# 04_Motor.net
KiCad netlist of a schematic drawn in Altium Designer
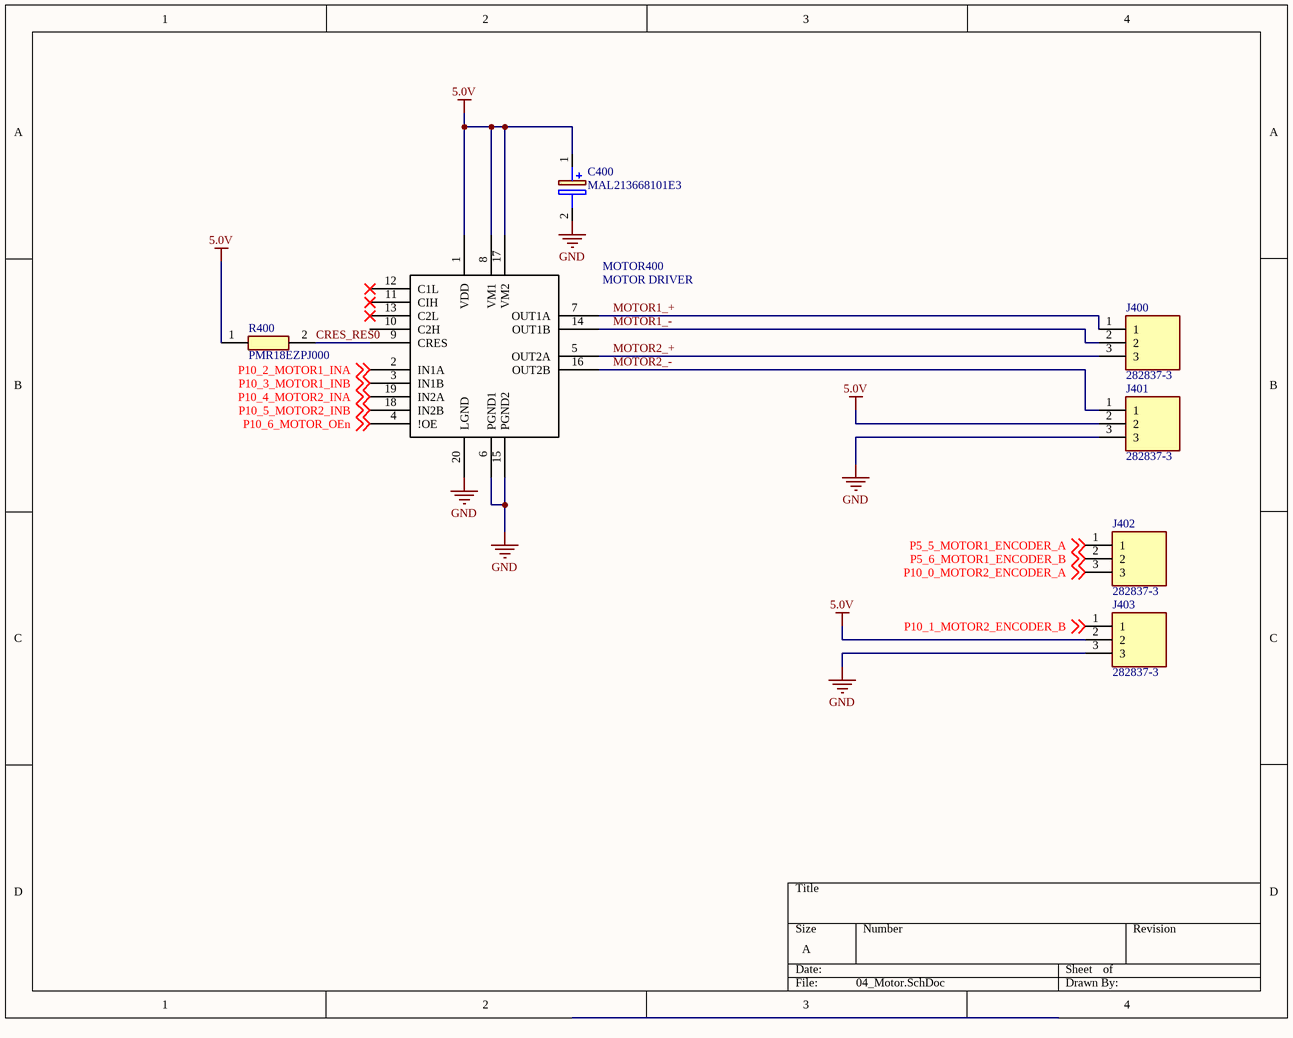
[diagram p0: 04_Motor.SchDoc]

(export (version "E")
  (design (tool "Eeschema 10.0.6"))
  (components
    (comp (ref "C400")
      (value "MAL213668101E3")
      (footprint "SamacSys:CAPPRD500W60D1050H1750")
      (description "Capacitor Polarised")
      (libsource (lib "100ufElectrolyticCap") (part "MAL213668101E3"))
    )
    (comp (ref "J400")
      (value "282837-3")
      (footprint "SamacSys:2828373")
      (description "Connector")
      (libsource (lib "3PinConnector") (part "282837-3"))
    )
    (comp (ref "J401")
      (value "282837-3")
      (footprint "SamacSys:2828373")
      (description "Connector")
      (libsource (lib "3PinConnector") (part "282837-3"))
    )
    (comp (ref "J402")
      (value "282837-3")
      (footprint "SamacSys:2828373")
      (description "Connector")
      (libsource (lib "3PinConnector") (part "282837-3"))
    )
    (comp (ref "J403")
      (value "282837-3")
      (footprint "SamacSys:2828373")
      (description "Connector")
      (libsource (lib "3PinConnector") (part "282837-3"))
    )
    (comp (ref "MOTOR400")
      (value "MOTOR DRIVER")
      (footprint "SOP65P640X120-20N")
      (libsource (lib "SOP65P640X120-20N") (part "SOP65P64X1"))
    )
    (comp (ref "R400")
      (value "PMR18EZPJ000")
      (footprint "SamacSys:RESC3216X42N")
      (description "Resistor")
      (libsource (lib "0ohmRes") (part "PMR18EZPJ000"))
    )
  )
  (nets
    (net (code "1") (name "/CRES_RES0") (class "Default")
      (node (ref "MOTOR400") (pin "9") (pinfunction "CRES_9") (pintype "passive"))
      (node (ref "R400") (pin "2") (pinfunction "2_2") (pintype "passive"))
    )
    (net (code "2") (name "/MOTOR1_+") (class "Default")
      (node (ref "J400") (pin "1") (pinfunction "1_1") (pintype "passive"))
      (node (ref "MOTOR400") (pin "7") (pinfunction "OUT1A_7") (pintype "passive"))
    )
    (net (code "3") (name "/MOTOR1_-") (class "Default")
      (node (ref "J400") (pin "2") (pinfunction "2_2") (pintype "passive"))
      (node (ref "MOTOR400") (pin "14") (pinfunction "OUT1B_14") (pintype "passive"))
    )
    (net (code "4") (name "/MOTOR2_+") (class "Default")
      (node (ref "J400") (pin "3") (pinfunction "3_3") (pintype "passive"))
      (node (ref "MOTOR400") (pin "5") (pinfunction "OUT2A_5") (pintype "passive"))
    )
    (net (code "5") (name "/MOTOR2_-") (class "Default")
      (node (ref "J401") (pin "1") (pinfunction "1_1") (pintype "passive"))
      (node (ref "MOTOR400") (pin "16") (pinfunction "OUT2B_16") (pintype "passive"))
    )
    (net (code "6") (name "5.0V") (class "Default")
      (node (ref "C400") (pin "1") (pinfunction "+_1") (pintype "passive"))
      (node (ref "J401") (pin "2") (pinfunction "2_2") (pintype "passive"))
      (node (ref "J403") (pin "2") (pinfunction "2_2") (pintype "passive"))
      (node (ref "MOTOR400") (pin "1") (pinfunction "VDD_1") (pintype "passive"))
      (node (ref "MOTOR400") (pin "17") (pinfunction "VM2_17") (pintype "passive"))
      (node (ref "MOTOR400") (pin "8") (pinfunction "VM1_8") (pintype "passive"))
      (node (ref "R400") (pin "1") (pinfunction "1_1") (pintype "passive"))
    )
    (net (code "7") (name "GND") (class "Default")
      (node (ref "C400") (pin "2") (pinfunction "-_2") (pintype "passive"))
      (node (ref "J401") (pin "3") (pinfunction "3_3") (pintype "passive"))
      (node (ref "J403") (pin "3") (pinfunction "3_3") (pintype "passive"))
      (node (ref "MOTOR400") (pin "15") (pinfunction "PGND2_15") (pintype "passive"))
      (node (ref "MOTOR400") (pin "20") (pinfunction "LGND_20") (pintype "passive"))
      (node (ref "MOTOR400") (pin "6") (pinfunction "PGND1_6") (pintype "passive"))
    )
    (net (code "8") (name "P5_5_MOTOR1_ENCODER_A") (class "Default")
      (node (ref "J402") (pin "1") (pinfunction "1_1") (pintype "passive"))
    )
    (net (code "9") (name "P5_6_MOTOR1_ENCODER_B") (class "Default")
      (node (ref "J402") (pin "2") (pinfunction "2_2") (pintype "passive"))
    )
    (net (code "10") (name "P10_0_MOTOR2_ENCODER_A") (class "Default")
      (node (ref "J402") (pin "3") (pinfunction "3_3") (pintype "passive"))
    )
    (net (code "11") (name "P10_1_MOTOR2_ENCODER_B") (class "Default")
      (node (ref "J403") (pin "1") (pinfunction "1_1") (pintype "passive"))
    )
    (net (code "12") (name "P10_2_MOTOR1_INA") (class "Default")
      (node (ref "MOTOR400") (pin "2") (pinfunction "IN1A_2") (pintype "passive"))
    )
    (net (code "13") (name "P10_3_MOTOR1_INB") (class "Default")
      (node (ref "MOTOR400") (pin "3") (pinfunction "IN1B_3") (pintype "passive"))
    )
    (net (code "14") (name "P10_4_MOTOR2_INA") (class "Default")
      (node (ref "MOTOR400") (pin "19") (pinfunction "IN2A_19") (pintype "passive"))
    )
    (net (code "15") (name "P10_5_MOTOR2_INB") (class "Default")
      (node (ref "MOTOR400") (pin "18") (pinfunction "IN2B_18") (pintype "passive"))
    )
    (net (code "16") (name "P10_6_MOTOR_OEn") (class "Default")
      (node (ref "MOTOR400") (pin "4") (pinfunction "!OE_4") (pintype "passive"))
    )
    (net (code "17") (name "unconnected-(MOTOR400-C1L-Pad12)") (class "Default")
      (node (ref "MOTOR400") (pin "12") (pinfunction "C1L_12") (pintype "passive+no_connect"))
    )
    (net (code "18") (name "unconnected-(MOTOR400-C2H-Pad10)") (class "Default")
      (node (ref "MOTOR400") (pin "10") (pinfunction "C2H_10") (pintype "passive"))
    )
    (net (code "19") (name "unconnected-(MOTOR400-C2L-Pad13)") (class "Default")
      (node (ref "MOTOR400") (pin "13") (pinfunction "C2L_13") (pintype "passive+no_connect"))
    )
    (net (code "20") (name "unconnected-(MOTOR400-CIH-Pad11)") (class "Default")
      (node (ref "MOTOR400") (pin "11") (pinfunction "CIH_11") (pintype "passive+no_connect"))
    )
  )
)
